# Trinket_Charger_Shield_F_052016.net
KiCad netlist of a schematic drawn in EAGLE
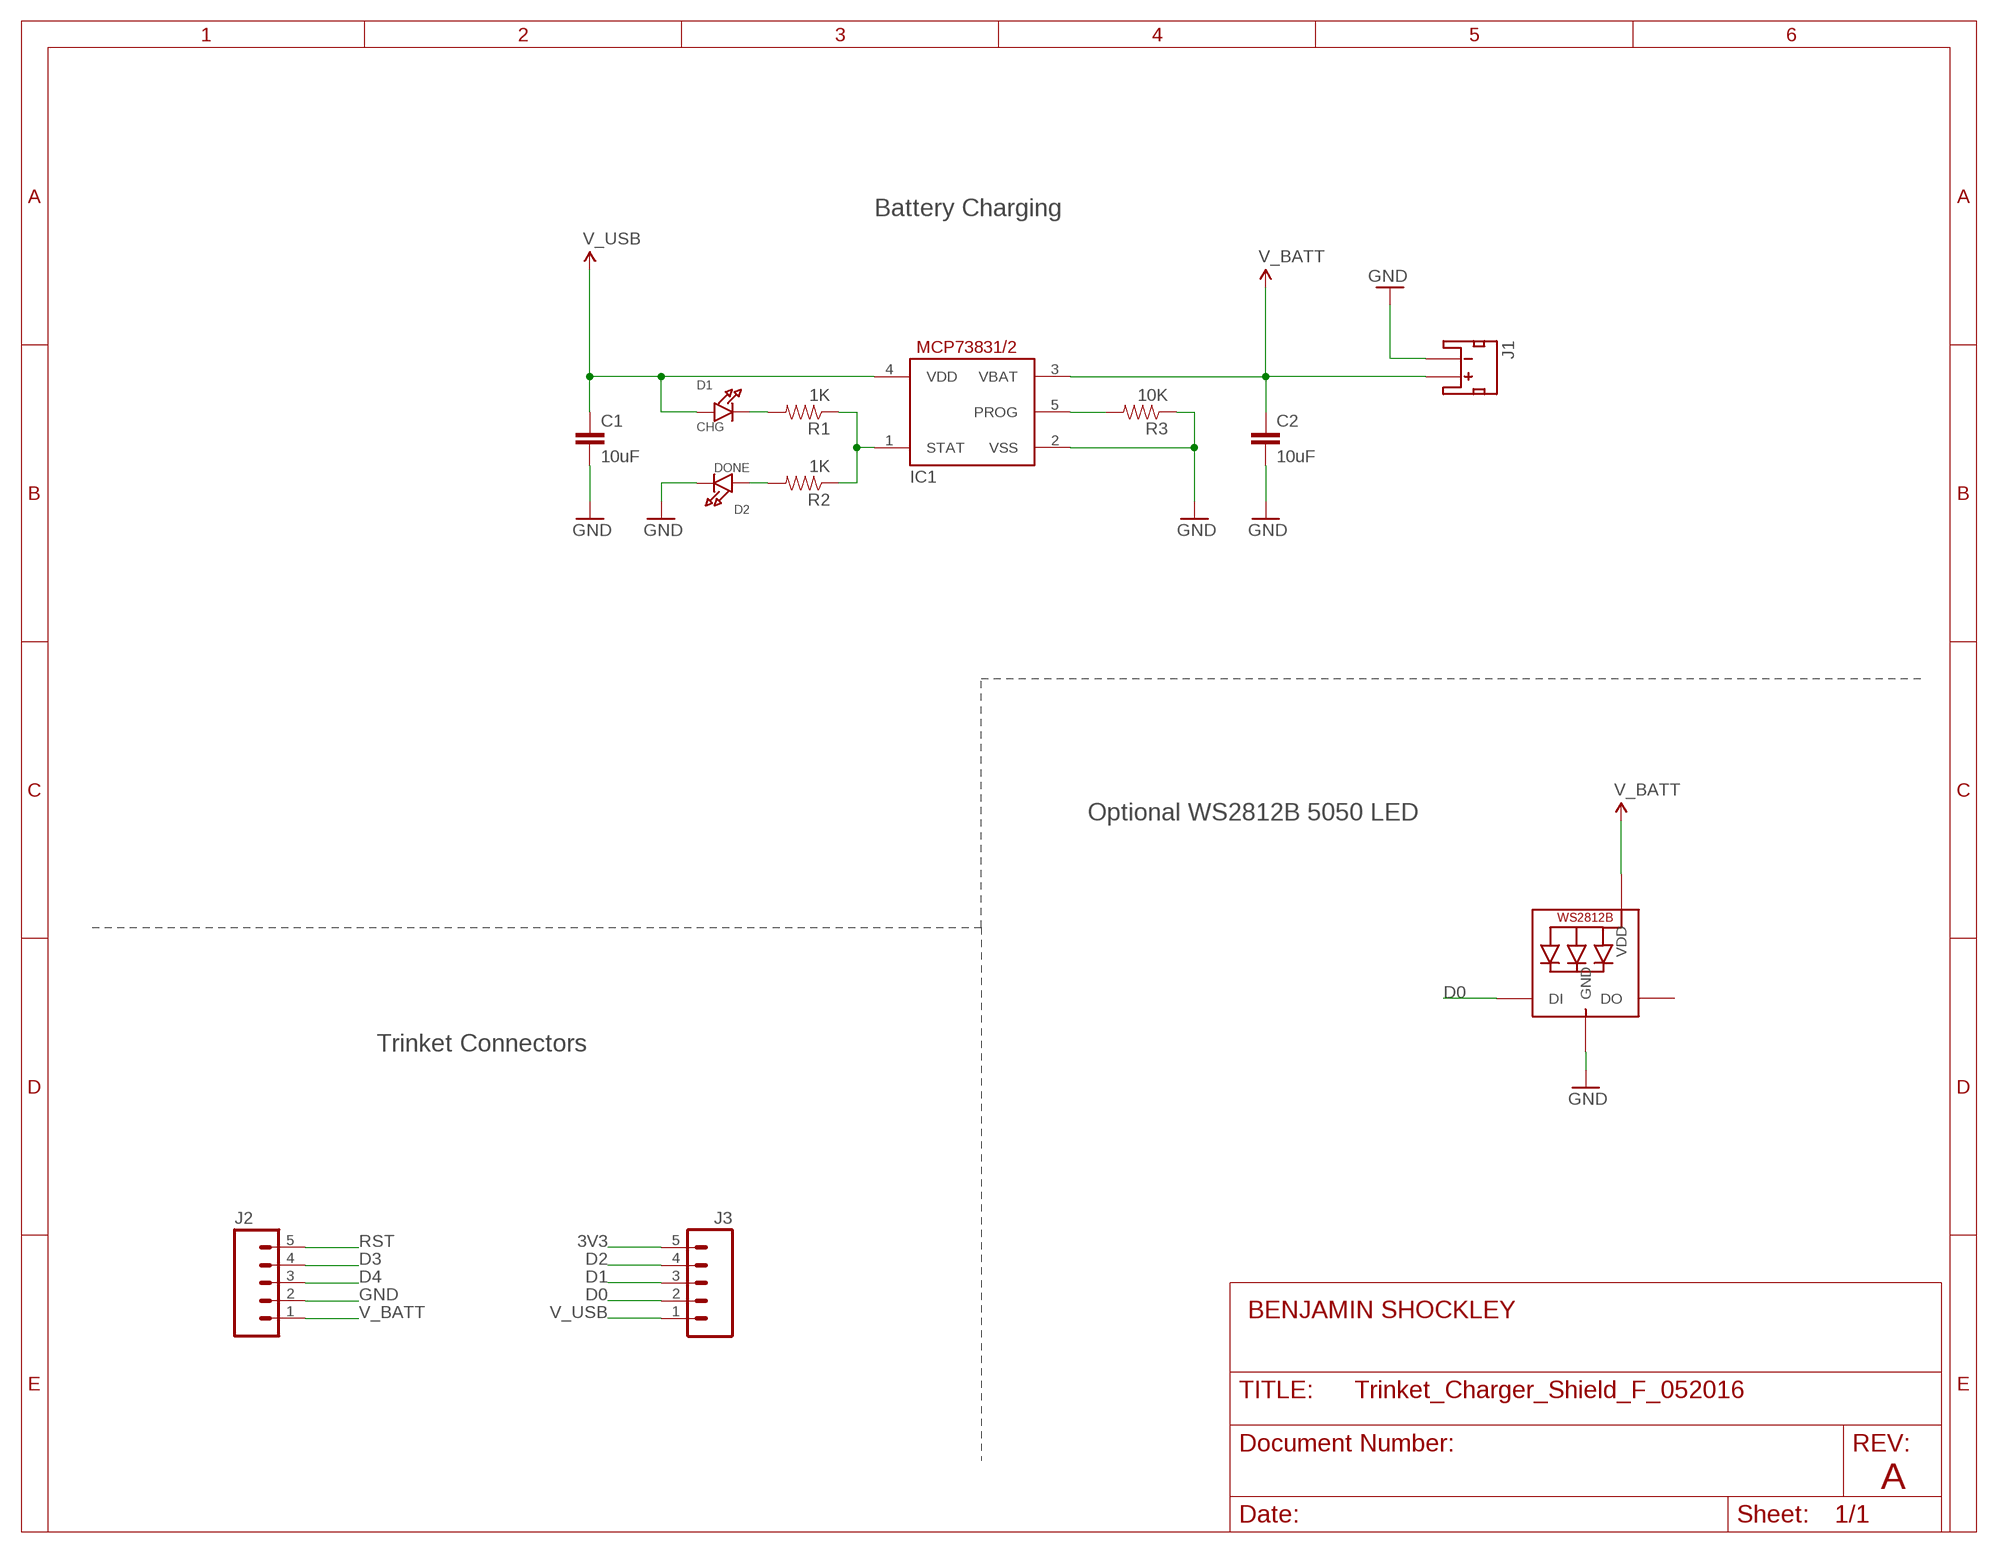
[diagram p0: schematic, sheet 1]

(export (version "E")
  (design (tool "Eeschema 10.0.6"))
  (components
    (comp (ref "C1")
      (value "10uF")
      (footprint "eagle-import:0805")
      (libsource (lib "eagle-import") (part "CAP0805"))
    )
    (comp (ref "C2")
      (value "10uF")
      (footprint "eagle-import:0805")
      (libsource (lib "eagle-import") (part "CAP0805"))
    )
    (comp (ref "D1")
      (value "CHG")
      (footprint "eagle-import:CHIPLED_0805_NOOUTLINE")
      (libsource (lib "eagle-import") (part "LED0805_NOOUTLINE"))
    )
    (comp (ref "D2")
      (value "DONE")
      (footprint "eagle-import:CHIPLED_0805_NOOUTLINE")
      (libsource (lib "eagle-import") (part "LED0805_NOOUTLINE"))
    )
    (comp (ref "IC1")
      (value "MCP73831/OT")
      (footprint "eagle-import:SOT23-5L")
      (libsource (lib "eagle-import") (part "MCP73831/OT"))
    )
    (comp (ref "J1")
      (value "JST_2MM_MALE")
      (footprint "eagle-import:JST-2-SMD")
      (libsource (lib "eagle-import") (part "JST_2MM_MALE"))
    )
    (comp (ref "J2")
      (value "M05NO_SILK")
      (footprint "eagle-import:1X05_NO_SILK")
      (libsource (lib "eagle-import") (part "M05NO_SILK"))
    )
    (comp (ref "J3")
      (value "M05NO_SILK")
      (footprint "eagle-import:1X05_NO_SILK")
      (libsource (lib "eagle-import") (part "M05NO_SILK"))
    )
    (comp (ref "LED")
      (value "WS2812B5050")
      (footprint "eagle-import:WS2812B")
      (libsource (lib "eagle-import") (part "WS2812B5050"))
    )
    (comp (ref "R1")
      (value "1K")
      (footprint "eagle-import:0805")
      (libsource (lib "eagle-import") (part "RESISTOR0805-RES"))
    )
    (comp (ref "R2")
      (value "1K")
      (footprint "eagle-import:0805")
      (libsource (lib "eagle-import") (part "RESISTOR0805-RES"))
    )
    (comp (ref "R3")
      (value "10K")
      (footprint "eagle-import:0805")
      (libsource (lib "eagle-import") (part "RESISTOR0805-RES"))
    )
  )
  (nets
    (net (code "1") (name "/3V3") (class "Default")
      (node (ref "J3") (pin "5") (pinfunction "5_5") (pintype "passive"))
    )
    (net (code "2") (name "/D0") (class "Default")
      (node (ref "J3") (pin "2") (pinfunction "2_2") (pintype "passive"))
      (node (ref "LED") (pin "4-DIN") (pinfunction "DI_4-DIN") (pintype "input"))
    )
    (net (code "3") (name "/D1") (class "Default")
      (node (ref "J3") (pin "3") (pinfunction "3_3") (pintype "passive"))
    )
    (net (code "4") (name "/D2") (class "Default")
      (node (ref "J3") (pin "4") (pinfunction "4_4") (pintype "passive"))
    )
    (net (code "5") (name "/D3") (class "Default")
      (node (ref "J2") (pin "4") (pinfunction "4_4") (pintype "passive"))
    )
    (net (code "6") (name "/D4") (class "Default")
      (node (ref "J2") (pin "3") (pinfunction "3_3") (pintype "passive"))
    )
    (net (code "7") (name "/RST") (class "Default")
      (node (ref "J2") (pin "5") (pinfunction "5_5") (pintype "passive"))
    )
    (net (code "8") (name "GND") (class "Default")
      (node (ref "C1") (pin "2") (pinfunction "2_2") (pintype "passive"))
      (node (ref "C2") (pin "2") (pinfunction "2_2") (pintype "passive"))
      (node (ref "D2") (pin "C") (pinfunction "C_C") (pintype "passive"))
      (node (ref "IC1") (pin "2") (pinfunction "VSS_2") (pintype "power_in"))
      (node (ref "J1") (pin "1") (pinfunction "-_1") (pintype "bidirectional"))
      (node (ref "J2") (pin "2") (pinfunction "2_2") (pintype "passive"))
      (node (ref "LED") (pin "3-GND") (pinfunction "GND_3-GND") (pintype "power_in"))
      (node (ref "R3") (pin "1") (pinfunction "1_1") (pintype "passive"))
    )
    (net (code "9") (name "Net-(D1-PadC)") (class "Default")
      (node (ref "D1") (pin "C") (pinfunction "C_C") (pintype "passive"))
      (node (ref "R1") (pin "2") (pinfunction "2_2") (pintype "passive"))
    )
    (net (code "10") (name "Net-(D2-PadA)") (class "Default")
      (node (ref "D2") (pin "A") (pinfunction "A_A") (pintype "passive"))
      (node (ref "R2") (pin "2") (pinfunction "2_2") (pintype "passive"))
    )
    (net (code "11") (name "Net-(IC1-PROG)") (class "Default")
      (node (ref "IC1") (pin "5") (pinfunction "PROG_5") (pintype "input"))
      (node (ref "R3") (pin "2") (pinfunction "2_2") (pintype "passive"))
    )
    (net (code "12") (name "Net-(IC1-STAT)") (class "Default")
      (node (ref "IC1") (pin "1") (pinfunction "STAT_1") (pintype "output"))
      (node (ref "R1") (pin "1") (pinfunction "1_1") (pintype "passive"))
      (node (ref "R2") (pin "1") (pinfunction "1_1") (pintype "passive"))
    )
    (net (code "13") (name "V_BATT") (class "Default")
      (node (ref "C2") (pin "1") (pinfunction "1_1") (pintype "passive"))
      (node (ref "IC1") (pin "3") (pinfunction "VBAT_3") (pintype "bidirectional"))
      (node (ref "J1") (pin "2") (pinfunction "+_2") (pintype "bidirectional"))
      (node (ref "J2") (pin "1") (pinfunction "1_1") (pintype "passive"))
      (node (ref "LED") (pin "1-VDD") (pinfunction "VDD_1-VDD") (pintype "power_in"))
    )
    (net (code "14") (name "V_USB") (class "Default")
      (node (ref "C1") (pin "1") (pinfunction "1_1") (pintype "passive"))
      (node (ref "D1") (pin "A") (pinfunction "A_A") (pintype "passive"))
      (node (ref "IC1") (pin "4") (pinfunction "VDD_4") (pintype "power_in"))
      (node (ref "J3") (pin "1") (pinfunction "1_1") (pintype "passive"))
    )
    (net (code "15") (name "unconnected-(J1-PAD1-PadNC1)") (class "Default")
      (node (ref "J1") (pin "NC1") (pinfunction "PAD1_NC1") (pintype "bidirectional"))
    )
    (net (code "16") (name "unconnected-(J1-PAD2-PadNC2)") (class "Default")
      (node (ref "J1") (pin "NC2") (pinfunction "PAD2_NC2") (pintype "bidirectional"))
    )
    (net (code "17") (name "unconnected-(LED-DO-Pad2-DOUT)") (class "Default")
      (node (ref "LED") (pin "2-DOUT") (pinfunction "DO_2-DOUT") (pintype "output"))
    )
  )
)
